# bb8_v2.net
KiCad netlist of a schematic drawn in Altium Designer
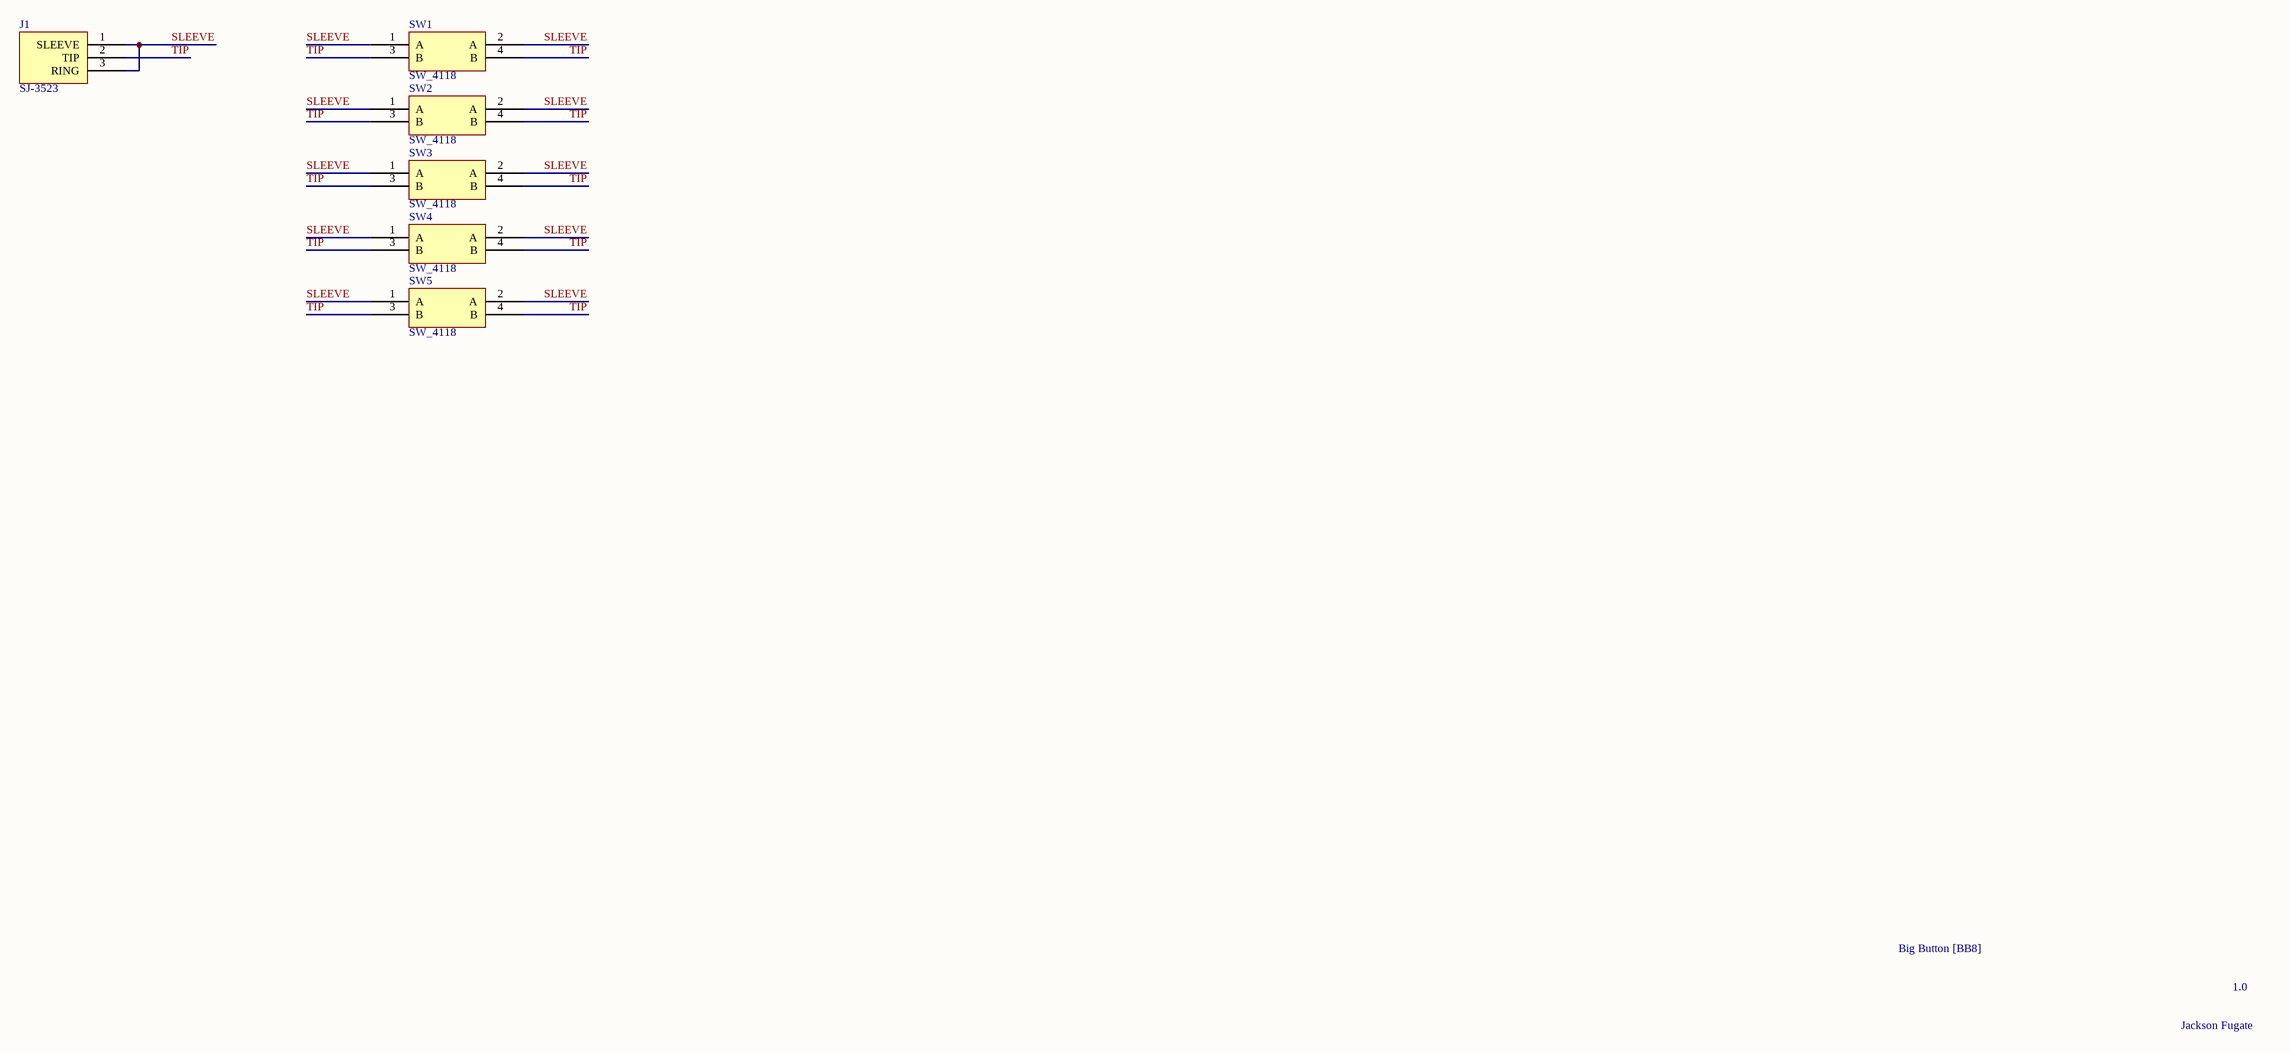
[diagram p0: bb8_v2.SchDoc]

(export (version "E")
  (design (tool "Eeschema 10.0.6"))
  (components
    (comp (ref "J1")
      (value "SJ-3523")
      (footprint "SJ-352X")
      (libsource (lib "JF_master_lib") (part "SJ-3523"))
    )
    (comp (ref "SW1")
      (value "SW_4118")
      (footprint "SW_4118")
      (libsource (lib "JF_master_lib") (part "SW_4118"))
    )
    (comp (ref "SW2")
      (value "SW_4118")
      (footprint "SW_4118")
      (libsource (lib "JF_master_lib") (part "SW_4118"))
    )
    (comp (ref "SW3")
      (value "SW_4118")
      (footprint "SW_4118")
      (libsource (lib "JF_master_lib") (part "SW_4118"))
    )
    (comp (ref "SW4")
      (value "SW_4118")
      (footprint "SW_4118")
      (libsource (lib "JF_master_lib") (part "SW_4118"))
    )
    (comp (ref "SW5")
      (value "SW_4118")
      (footprint "SW_4118")
      (libsource (lib "JF_master_lib") (part "SW_4118"))
    )
  )
  (nets
    (net (code "1") (name "/SLEEVE") (class "Default")
      (node (ref "J1") (pin "1") (pinfunction "SLEEVE_1") (pintype "passive"))
      (node (ref "J1") (pin "3") (pinfunction "RING_3") (pintype "passive"))
      (node (ref "SW1") (pin "1") (pinfunction "A_1") (pintype "passive"))
      (node (ref "SW1") (pin "2") (pinfunction "A_2") (pintype "passive"))
      (node (ref "SW2") (pin "1") (pinfunction "A_1") (pintype "passive"))
      (node (ref "SW2") (pin "2") (pinfunction "A_2") (pintype "passive"))
      (node (ref "SW3") (pin "1") (pinfunction "A_1") (pintype "passive"))
      (node (ref "SW3") (pin "2") (pinfunction "A_2") (pintype "passive"))
      (node (ref "SW4") (pin "1") (pinfunction "A_1") (pintype "passive"))
      (node (ref "SW4") (pin "2") (pinfunction "A_2") (pintype "passive"))
      (node (ref "SW5") (pin "1") (pinfunction "A_1") (pintype "passive"))
      (node (ref "SW5") (pin "2") (pinfunction "A_2") (pintype "passive"))
    )
    (net (code "2") (name "/TIP") (class "Default")
      (node (ref "J1") (pin "2") (pinfunction "TIP_2") (pintype "passive"))
      (node (ref "SW1") (pin "3") (pinfunction "B_3") (pintype "passive"))
      (node (ref "SW1") (pin "4") (pinfunction "B_4") (pintype "passive"))
      (node (ref "SW2") (pin "3") (pinfunction "B_3") (pintype "passive"))
      (node (ref "SW2") (pin "4") (pinfunction "B_4") (pintype "passive"))
      (node (ref "SW3") (pin "3") (pinfunction "B_3") (pintype "passive"))
      (node (ref "SW3") (pin "4") (pinfunction "B_4") (pintype "passive"))
      (node (ref "SW4") (pin "3") (pinfunction "B_3") (pintype "passive"))
      (node (ref "SW4") (pin "4") (pinfunction "B_4") (pintype "passive"))
      (node (ref "SW5") (pin "3") (pinfunction "B_3") (pintype "passive"))
      (node (ref "SW5") (pin "4") (pinfunction "B_4") (pintype "passive"))
    )
  )
)
